# Power.net
KiCad netlist of a schematic drawn in Altium Designer
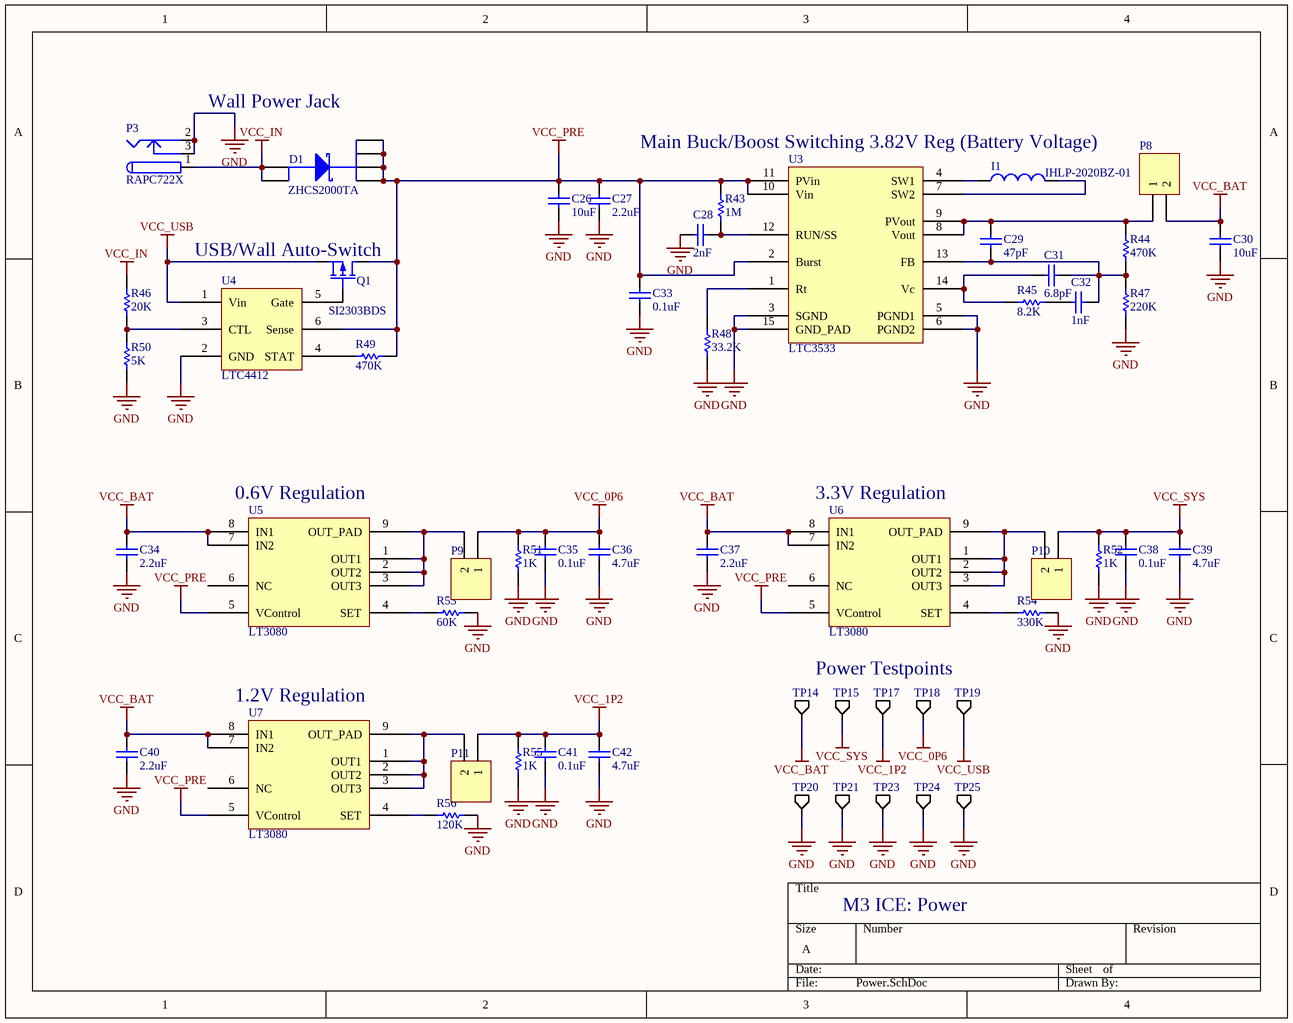
[diagram p0: Power.SchDoc]

(export (version "E")
  (design (tool "Eeschema 10.0.6"))
  (components
    (comp (ref "C26")
      (value "10uF")
      (footprint "0805")
      (description "Capacitor (Semiconductor SIM Model)")
      (fields (field (name "Comment") "Cap Chip") (field (name "PUBLISHER") "Altium Limited"))
      (libsource (lib "M3") (part "Cap Chip"))
    )
    (comp (ref "C27")
      (value "2.2uF")
      (footprint "1608[0603]")
      (description "Capacitor (Semiconductor SIM Model)")
      (fields (field (name "Comment") "Cap Semi") (field (name "PUBLISHER") "Altium Limited"))
      (libsource (lib "Miscellaneous Devices") (part "Cap Semi"))
    )
    (comp (ref "C28")
      (value "2nF")
      (footprint "1608[0603]")
      (description "Capacitor (Semiconductor SIM Model)")
      (fields (field (name "Comment") "Cap Semi") (field (name "PUBLISHER") "Altium Limited"))
      (libsource (lib "Miscellaneous Devices") (part "Cap Semi"))
    )
    (comp (ref "C29")
      (value "47pF")
      (footprint "1608[0603]")
      (description "Capacitor (Semiconductor SIM Model)")
      (fields (field (name "Comment") "Cap Semi") (field (name "PUBLISHER") "Altium Limited"))
      (libsource (lib "Miscellaneous Devices") (part "Cap Semi"))
    )
    (comp (ref "C30")
      (value "10uF")
      (footprint "0805")
      (description "Capacitor (Semiconductor SIM Model)")
      (fields (field (name "Comment") "Cap Chip") (field (name "PUBLISHER") "Altium Limited"))
      (libsource (lib "M3") (part "Cap Chip"))
    )
    (comp (ref "C31")
      (value "6.8pF")
      (footprint "1608[0603]")
      (description "Capacitor (Semiconductor SIM Model)")
      (fields (field (name "Comment") "Cap Semi") (field (name "PUBLISHER") "Altium Limited"))
      (libsource (lib "Miscellaneous Devices") (part "Cap Semi"))
    )
    (comp (ref "C32")
      (value "1nF")
      (footprint "1608[0603]")
      (description "Capacitor (Semiconductor SIM Model)")
      (fields (field (name "Comment") "Cap Semi") (field (name "PUBLISHER") "Altium Limited"))
      (libsource (lib "Miscellaneous Devices") (part "Cap Semi"))
    )
    (comp (ref "C33")
      (value "0.1uF")
      (footprint "1608[0603]")
      (description "Capacitor (Semiconductor SIM Model)")
      (fields (field (name "Comment") "Cap Semi") (field (name "PUBLISHER") "Altium Limited"))
      (libsource (lib "Miscellaneous Devices") (part "Cap Semi"))
    )
    (comp (ref "C34")
      (value "2.2uF")
      (footprint "1608[0603]")
      (description "Capacitor (Semiconductor SIM Model)")
      (fields (field (name "Comment") "Cap Semi") (field (name "PUBLISHER") "Altium Limited"))
      (libsource (lib "Miscellaneous Devices") (part "Cap Semi"))
    )
    (comp (ref "C35")
      (value "0.1uF")
      (footprint "1608[0603]")
      (description "Capacitor (Semiconductor SIM Model)")
      (fields (field (name "Comment") "Cap Semi") (field (name "PUBLISHER") "Altium Limited"))
      (libsource (lib "Miscellaneous Devices") (part "Cap Semi"))
    )
    (comp (ref "C36")
      (value "4.7uF")
      (footprint "0805")
      (description "Capacitor (Semiconductor SIM Model)")
      (fields (field (name "Comment") "Cap Chip") (field (name "PUBLISHER") "Altium Limited"))
      (libsource (lib "M3") (part "Cap Chip"))
    )
    (comp (ref "C37")
      (value "2.2uF")
      (footprint "1608[0603]")
      (description "Capacitor (Semiconductor SIM Model)")
      (fields (field (name "Comment") "Cap Semi") (field (name "PUBLISHER") "Altium Limited"))
      (libsource (lib "Miscellaneous Devices") (part "Cap Semi"))
    )
    (comp (ref "C38")
      (value "0.1uF")
      (footprint "1608[0603]")
      (description "Capacitor (Semiconductor SIM Model)")
      (fields (field (name "Comment") "Cap Semi") (field (name "PUBLISHER") "Altium Limited"))
      (libsource (lib "Miscellaneous Devices") (part "Cap Semi"))
    )
    (comp (ref "C39")
      (value "4.7uF")
      (footprint "0805")
      (description "Capacitor (Semiconductor SIM Model)")
      (fields (field (name "Comment") "Cap Chip") (field (name "PUBLISHER") "Altium Limited"))
      (libsource (lib "M3") (part "Cap Chip"))
    )
    (comp (ref "C40")
      (value "2.2uF")
      (footprint "1608[0603]")
      (description "Capacitor (Semiconductor SIM Model)")
      (fields (field (name "Comment") "Cap Semi") (field (name "PUBLISHER") "Altium Limited"))
      (libsource (lib "Miscellaneous Devices") (part "Cap Semi"))
    )
    (comp (ref "C41")
      (value "0.1uF")
      (footprint "1608[0603]")
      (description "Capacitor (Semiconductor SIM Model)")
      (fields (field (name "Comment") "Cap Semi") (field (name "PUBLISHER") "Altium Limited"))
      (libsource (lib "Miscellaneous Devices") (part "Cap Semi"))
    )
    (comp (ref "C42")
      (value "4.7uF")
      (footprint "0805")
      (description "Capacitor (Semiconductor SIM Model)")
      (fields (field (name "Comment") "Cap Chip") (field (name "PUBLISHER") "Altium Limited"))
      (libsource (lib "M3") (part "Cap Chip"))
    )
    (comp (ref "D1")
      (value "ZHCS2000TA")
      (footprint "SOT23-6_L")
      (description "Schottky Diode")
      (fields (field (name "PUBLISHER") "Altium Limited"))
      (libsource (lib "M3") (part "ZHCS2000TA"))
    )
    (comp (ref "I1")
      (value "IHLP-2020BZ-01")
      (footprint "INDUCTOR_5.49mm_5.18mm")
      (description "IHLP2020BZER2R2M01")
      (libsource (lib "M3") (part "Inductor IHLP-2020BZ-01"))
    )
    (comp (ref "P3")
      (value "RAPC722X")
      (footprint "RAPC722X")
      (description "CONN POWERJACK MINI R/A T/H")
      (libsource (lib "M3") (part "RAPC722X"))
    )
    (comp (ref "P8")
      (value "Header 2")
      (footprint "HDR1X2")
      (description "Header, 2-Pin")
      (fields (field (name "PUBLISHER") "Altium Limited"))
      (libsource (lib "Miscellaneous Connectors") (part "Header 2"))
    )
    (comp (ref "P9")
      (value "Header 2")
      (footprint "HDR1X2")
      (description "Header, 2-Pin")
      (fields (field (name "PUBLISHER") "Altium Limited"))
      (libsource (lib "") (part "Header 2_1"))
    )
    (comp (ref "P10")
      (value "Header 2")
      (footprint "HDR1X2")
      (description "Header, 2-Pin")
      (fields (field (name "PUBLISHER") "Altium Limited"))
      (libsource (lib "") (part "Header 2_1"))
    )
    (comp (ref "P11")
      (value "Header 2")
      (footprint "HDR1X2")
      (description "Header, 2-Pin")
      (fields (field (name "PUBLISHER") "Altium Limited"))
      (libsource (lib "") (part "Header 2_1"))
    )
    (comp (ref "Q1")
      (value "SI2303BDS")
      (footprint "SOT-23_N")
      (description "P-Channel MOSFET")
      (libsource (lib "M3") (part "SI2303BDS"))
    )
    (comp (ref "R43")
      (value "1M")
      (footprint "0603")
      (description "Semiconductor Resistor")
      (fields (field (name "Comment") "Res Chip") (field (name "PUBLISHER") "Altium Limited"))
      (libsource (lib "M3") (part "Res Chip"))
    )
    (comp (ref "R44")
      (value "470K")
      (footprint "0603")
      (description "Semiconductor Resistor")
      (fields (field (name "Comment") "Res Chip") (field (name "PUBLISHER") "Altium Limited"))
      (libsource (lib "M3") (part "Res Chip"))
    )
    (comp (ref "R45")
      (value "8.2K")
      (footprint "0603")
      (description "Semiconductor Resistor")
      (fields (field (name "Comment") "Res Chip") (field (name "PUBLISHER") "Altium Limited"))
      (libsource (lib "M3") (part "Res Chip"))
    )
    (comp (ref "R46")
      (value "20K")
      (footprint "0603")
      (description "Semiconductor Resistor")
      (fields (field (name "Comment") "Res Chip") (field (name "PUBLISHER") "Altium Limited"))
      (libsource (lib "M3") (part "Res Chip"))
    )
    (comp (ref "R47")
      (value "220K")
      (footprint "0603")
      (description "Semiconductor Resistor")
      (fields (field (name "Comment") "Res Chip") (field (name "PUBLISHER") "Altium Limited"))
      (libsource (lib "M3") (part "Res Chip"))
    )
    (comp (ref "R48")
      (value "33.2K")
      (footprint "0603")
      (description "Semiconductor Resistor")
      (fields (field (name "Comment") "Res Chip") (field (name "PUBLISHER") "Altium Limited"))
      (libsource (lib "M3") (part "Res Chip"))
    )
    (comp (ref "R49")
      (value "470K")
      (footprint "0603")
      (description "Semiconductor Resistor")
      (fields (field (name "Comment") "Res Chip") (field (name "PUBLISHER") "Altium Limited"))
      (libsource (lib "M3") (part "Res Chip"))
    )
    (comp (ref "R50")
      (value "5K")
      (footprint "0603")
      (description "Semiconductor Resistor")
      (fields (field (name "Comment") "Res Chip") (field (name "PUBLISHER") "Altium Limited"))
      (libsource (lib "M3") (part "Res Chip"))
    )
    (comp (ref "R51")
      (value "1K")
      (footprint "0603")
      (description "Semiconductor Resistor")
      (fields (field (name "Comment") "Res Chip") (field (name "PUBLISHER") "Altium Limited"))
      (libsource (lib "M3") (part "Res Chip"))
    )
    (comp (ref "R52")
      (value "1K")
      (footprint "0603")
      (description "Semiconductor Resistor")
      (fields (field (name "Comment") "Res Chip") (field (name "PUBLISHER") "Altium Limited"))
      (libsource (lib "M3") (part "Res Chip"))
    )
    (comp (ref "R53")
      (value "60K")
      (footprint "0603")
      (description "Semiconductor Resistor")
      (fields (field (name "Comment") "Res Chip") (field (name "PUBLISHER") "Altium Limited"))
      (libsource (lib "M3") (part "Res Chip"))
    )
    (comp (ref "R54")
      (value "330K")
      (footprint "0603")
      (description "Semiconductor Resistor")
      (fields (field (name "Comment") "Res Chip") (field (name "PUBLISHER") "Altium Limited"))
      (libsource (lib "M3") (part "Res Chip"))
    )
    (comp (ref "R55")
      (value "1K")
      (footprint "0603")
      (description "Semiconductor Resistor")
      (fields (field (name "Comment") "Res Chip") (field (name "PUBLISHER") "Altium Limited"))
      (libsource (lib "M3") (part "Res Chip"))
    )
    (comp (ref "R56")
      (value "120K")
      (footprint "0603")
      (description "Semiconductor Resistor")
      (fields (field (name "Comment") "Res Chip") (field (name "PUBLISHER") "Altium Limited"))
      (libsource (lib "M3") (part "Res Chip"))
    )
    (comp (ref "TP14") (value "TP") (footprint "TP") (libsource (lib "M3") (part "TP")))
    (comp (ref "TP15") (value "TP") (footprint "TP") (libsource (lib "M3") (part "TP")))
    (comp (ref "TP17") (value "TP") (footprint "TP") (libsource (lib "M3") (part "TP")))
    (comp (ref "TP18") (value "TP") (footprint "TP") (libsource (lib "M3") (part "TP")))
    (comp (ref "TP19") (value "TP") (footprint "TP") (libsource (lib "M3") (part "TP")))
    (comp (ref "TP20") (value "TP") (footprint "TP") (libsource (lib "M3") (part "TP")))
    (comp (ref "TP21") (value "TP") (footprint "TP") (libsource (lib "M3") (part "TP")))
    (comp (ref "TP23") (value "TP") (footprint "TP") (libsource (lib "M3") (part "TP")))
    (comp (ref "TP24") (value "TP") (footprint "TP") (libsource (lib "M3") (part "TP")))
    (comp (ref "TP25") (value "TP") (footprint "TP") (libsource (lib "M3") (part "TP")))
    (comp (ref "U3") (value "LTC3533") (footprint "14-WFDFN") (libsource (lib "M3") (part "LTC3533")))
    (comp (ref "U4") (value "LTC4412") (footprint "SOT23-6_L") (libsource (lib "M3") (part "LTC4412")))
    (comp (ref "U5") (value "LT3080") (footprint "MSOP-8") (libsource (lib "M3") (part "LT3080")))
    (comp (ref "U6") (value "LT3080") (footprint "MSOP-8") (libsource (lib "M3") (part "LT3080")))
    (comp (ref "U7") (value "LT3080") (footprint "MSOP-8") (libsource (lib "M3") (part "LT3080")))
  )
  (nets
    (net (code "1") (name "GND") (class "Default")
      (node (ref "C26") (pin "1") (pinfunction "1_1") (pintype "passive"))
      (node (ref "C27") (pin "1") (pinfunction "1_1") (pintype "passive"))
      (node (ref "C28") (pin "2") (pinfunction "2_2") (pintype "passive"))
      (node (ref "C30") (pin "1") (pinfunction "1_1") (pintype "passive"))
      (node (ref "C33") (pin "1") (pinfunction "1_1") (pintype "passive"))
      (node (ref "C34") (pin "1") (pinfunction "1_1") (pintype "passive"))
      (node (ref "C35") (pin "1") (pinfunction "1_1") (pintype "passive"))
      (node (ref "C36") (pin "1") (pinfunction "1_1") (pintype "passive"))
      (node (ref "C37") (pin "1") (pinfunction "1_1") (pintype "passive"))
      (node (ref "C38") (pin "1") (pinfunction "1_1") (pintype "passive"))
      (node (ref "C39") (pin "1") (pinfunction "1_1") (pintype "passive"))
      (node (ref "C40") (pin "1") (pinfunction "1_1") (pintype "passive"))
      (node (ref "C41") (pin "1") (pinfunction "1_1") (pintype "passive"))
      (node (ref "C42") (pin "1") (pinfunction "1_1") (pintype "passive"))
      (node (ref "P3") (pin "2") (pinfunction "2_2") (pintype "power_in"))
      (node (ref "P3") (pin "3") (pinfunction "3_3") (pintype "power_in"))
      (node (ref "R47") (pin "2") (pinfunction "2_2") (pintype "passive"))
      (node (ref "R48") (pin "1") (pinfunction "1_1") (pintype "passive"))
      (node (ref "R50") (pin "1") (pinfunction "1_1") (pintype "passive"))
      (node (ref "R51") (pin "1") (pinfunction "1_1") (pintype "passive"))
      (node (ref "R52") (pin "1") (pinfunction "1_1") (pintype "passive"))
      (node (ref "R53") (pin "1") (pinfunction "1_1") (pintype "passive"))
      (node (ref "R54") (pin "1") (pinfunction "1_1") (pintype "passive"))
      (node (ref "R55") (pin "1") (pinfunction "1_1") (pintype "passive"))
      (node (ref "R56") (pin "1") (pinfunction "1_1") (pintype "passive"))
      (node (ref "TP20") (pin "1") (pinfunction "A_1") (pintype "passive"))
      (node (ref "TP21") (pin "1") (pinfunction "A_1") (pintype "passive"))
      (node (ref "TP23") (pin "1") (pinfunction "A_1") (pintype "passive"))
      (node (ref "TP24") (pin "1") (pinfunction "A_1") (pintype "passive"))
      (node (ref "TP25") (pin "1") (pinfunction "A_1") (pintype "passive"))
      (node (ref "U3") (pin "15") (pinfunction "GND_PAD_15") (pintype "passive"))
      (node (ref "U3") (pin "3") (pinfunction "SGND_3") (pintype "passive"))
      (node (ref "U3") (pin "5") (pinfunction "PGND1_5") (pintype "passive"))
      (node (ref "U3") (pin "6") (pinfunction "PGND2_6") (pintype "passive"))
      (node (ref "U4") (pin "2") (pinfunction "GND_2") (pintype "passive"))
    )
    (net (code "2") (name "Net-(C32-Pad2)") (class "Default")
      (node (ref "C32") (pin "2") (pinfunction "2_2") (pintype "passive"))
      (node (ref "R45") (pin "1") (pinfunction "1_1") (pintype "passive"))
    )
    (net (code "3") (name "Net-(Q1-G)") (class "Default")
      (node (ref "Q1") (pin "1") (pinfunction "G_1") (pintype "passive"))
      (node (ref "U4") (pin "5") (pinfunction "Gate_5") (pintype "passive"))
    )
    (net (code "4") (name "Net-(U3-FB)") (class "Default")
      (node (ref "C29") (pin "1") (pinfunction "1_1") (pintype "passive"))
      (node (ref "C31") (pin "1") (pinfunction "1_1") (pintype "passive"))
      (node (ref "C32") (pin "1") (pinfunction "1_1") (pintype "passive"))
      (node (ref "R44") (pin "1") (pinfunction "1_1") (pintype "passive"))
      (node (ref "R47") (pin "1") (pinfunction "1_1") (pintype "passive"))
      (node (ref "U3") (pin "13") (pinfunction "FB_13") (pintype "passive"))
    )
    (net (code "5") (name "Net-(U3-PVout)") (class "Default")
      (node (ref "C29") (pin "2") (pinfunction "2_2") (pintype "passive"))
      (node (ref "P8") (pin "1") (pinfunction "1_1") (pintype "passive"))
      (node (ref "R44") (pin "2") (pinfunction "2_2") (pintype "passive"))
      (node (ref "U3") (pin "8") (pinfunction "Vout_8") (pintype "passive"))
      (node (ref "U3") (pin "9") (pinfunction "PVout_9") (pintype "passive"))
    )
    (net (code "6") (name "Net-(U3-RUN{slash}SS)") (class "Default")
      (node (ref "C28") (pin "1") (pinfunction "1_1") (pintype "passive"))
      (node (ref "R43") (pin "1") (pinfunction "1_1") (pintype "passive"))
      (node (ref "U3") (pin "12") (pinfunction "RUN/SS_12") (pintype "passive"))
    )
    (net (code "7") (name "Net-(U3-Rt)") (class "Default")
      (node (ref "R48") (pin "2") (pinfunction "2_2") (pintype "passive"))
      (node (ref "U3") (pin "1") (pinfunction "Rt_1") (pintype "passive"))
    )
    (net (code "8") (name "Net-(U3-SW1)") (class "Default")
      (node (ref "I1") (pin "1") (pinfunction "1_1") (pintype "passive"))
      (node (ref "U3") (pin "4") (pinfunction "SW1_4") (pintype "passive"))
    )
    (net (code "9") (name "Net-(U3-SW2)") (class "Default")
      (node (ref "I1") (pin "2") (pinfunction "2_2") (pintype "passive"))
      (node (ref "U3") (pin "7") (pinfunction "SW2_7") (pintype "passive"))
    )
    (net (code "10") (name "Net-(U3-Vc)") (class "Default")
      (node (ref "C31") (pin "2") (pinfunction "2_2") (pintype "passive"))
      (node (ref "R45") (pin "2") (pinfunction "2_2") (pintype "passive"))
      (node (ref "U3") (pin "14") (pinfunction "Vc_14") (pintype "passive"))
    )
    (net (code "11") (name "Net-(U4-CTL)") (class "Default")
      (node (ref "R46") (pin "1") (pinfunction "1_1") (pintype "passive"))
      (node (ref "R50") (pin "2") (pinfunction "2_2") (pintype "passive"))
      (node (ref "U4") (pin "3") (pinfunction "CTL_3") (pintype "passive"))
    )
    (net (code "12") (name "Net-(U4-STAT)") (class "Default")
      (node (ref "R49") (pin "2") (pinfunction "2_2") (pintype "passive"))
      (node (ref "U4") (pin "4") (pinfunction "STAT_4") (pintype "passive"))
    )
    (net (code "13") (name "Net-(U5-OUT1)") (class "Default")
      (node (ref "P9") (pin "2") (pinfunction "2_2") (pintype "passive"))
      (node (ref "U5") (pin "1") (pinfunction "OUT1_1") (pintype "passive"))
      (node (ref "U5") (pin "2") (pinfunction "OUT2_2") (pintype "passive"))
      (node (ref "U5") (pin "3") (pinfunction "OUT3_3") (pintype "passive"))
      (node (ref "U5") (pin "9") (pinfunction "OUT_PAD_9") (pintype "passive"))
    )
    (net (code "14") (name "Net-(U5-SET)") (class "Default")
      (node (ref "R53") (pin "2") (pinfunction "2_2") (pintype "passive"))
      (node (ref "U5") (pin "4") (pinfunction "SET_4") (pintype "passive"))
    )
    (net (code "15") (name "Net-(U6-OUT1)") (class "Default")
      (node (ref "P10") (pin "2") (pinfunction "2_2") (pintype "passive"))
      (node (ref "U6") (pin "1") (pinfunction "OUT1_1") (pintype "passive"))
      (node (ref "U6") (pin "2") (pinfunction "OUT2_2") (pintype "passive"))
      (node (ref "U6") (pin "3") (pinfunction "OUT3_3") (pintype "passive"))
      (node (ref "U6") (pin "9") (pinfunction "OUT_PAD_9") (pintype "passive"))
    )
    (net (code "16") (name "Net-(U6-SET)") (class "Default")
      (node (ref "R54") (pin "2") (pinfunction "2_2") (pintype "passive"))
      (node (ref "U6") (pin "4") (pinfunction "SET_4") (pintype "passive"))
    )
    (net (code "17") (name "Net-(U7-OUT1)") (class "Default")
      (node (ref "P11") (pin "2") (pinfunction "2_2") (pintype "passive"))
      (node (ref "U7") (pin "1") (pinfunction "OUT1_1") (pintype "passive"))
      (node (ref "U7") (pin "2") (pinfunction "OUT2_2") (pintype "passive"))
      (node (ref "U7") (pin "3") (pinfunction "OUT3_3") (pintype "passive"))
      (node (ref "U7") (pin "9") (pinfunction "OUT_PAD_9") (pintype "passive"))
    )
    (net (code "18") (name "Net-(U7-SET)") (class "Default")
      (node (ref "R56") (pin "2") (pinfunction "2_2") (pintype "passive"))
      (node (ref "U7") (pin "4") (pinfunction "SET_4") (pintype "passive"))
    )
    (net (code "19") (name "VCC_0P6") (class "Default")
      (node (ref "C35") (pin "2") (pinfunction "2_2") (pintype "passive"))
      (node (ref "C36") (pin "2") (pinfunction "2_2") (pintype "passive"))
      (node (ref "P9") (pin "1") (pinfunction "1_1") (pintype "passive"))
      (node (ref "R51") (pin "2") (pinfunction "2_2") (pintype "passive"))
      (node (ref "TP18") (pin "1") (pinfunction "A_1") (pintype "passive"))
    )
    (net (code "20") (name "VCC_1P2") (class "Default")
      (node (ref "C41") (pin "2") (pinfunction "2_2") (pintype "passive"))
      (node (ref "C42") (pin "2") (pinfunction "2_2") (pintype "passive"))
      (node (ref "P11") (pin "1") (pinfunction "1_1") (pintype "passive"))
      (node (ref "R55") (pin "2") (pinfunction "2_2") (pintype "passive"))
      (node (ref "TP17") (pin "1") (pinfunction "A_1") (pintype "passive"))
    )
    (net (code "21") (name "VCC_BAT") (class "Default")
      (node (ref "C30") (pin "2") (pinfunction "2_2") (pintype "passive"))
      (node (ref "C34") (pin "2") (pinfunction "2_2") (pintype "passive"))
      (node (ref "C37") (pin "2") (pinfunction "2_2") (pintype "passive"))
      (node (ref "C40") (pin "2") (pinfunction "2_2") (pintype "passive"))
      (node (ref "P8") (pin "2") (pinfunction "2_2") (pintype "passive"))
      (node (ref "TP14") (pin "1") (pinfunction "A_1") (pintype "passive"))
      (node (ref "U5") (pin "7") (pinfunction "IN2_7") (pintype "passive"))
      (node (ref "U5") (pin "8") (pinfunction "IN1_8") (pintype "passive"))
      (node (ref "U6") (pin "7") (pinfunction "IN2_7") (pintype "passive"))
      (node (ref "U6") (pin "8") (pinfunction "IN1_8") (pintype "passive"))
      (node (ref "U7") (pin "7") (pinfunction "IN2_7") (pintype "passive"))
      (node (ref "U7") (pin "8") (pinfunction "IN1_8") (pintype "passive"))
    )
    (net (code "22") (name "VCC_IN") (class "Default")
      (node (ref "D1") (pin "3") (pinfunction "A_3") (pintype "passive"))
      (node (ref "D1") (pin "4") (pinfunction "A_4") (pintype "passive"))
      (node (ref "P3") (pin "1") (pinfunction "1_1") (pintype "power_in"))
      (node (ref "R46") (pin "2") (pinfunction "2_2") (pintype "passive"))
    )
    (net (code "23") (name "VCC_PRE") (class "Default")
      (node (ref "C26") (pin "2") (pinfunction "2_2") (pintype "passive"))
      (node (ref "C27") (pin "2") (pinfunction "2_2") (pintype "passive"))
      (node (ref "C33") (pin "2") (pinfunction "2_2") (pintype "passive"))
      (node (ref "D1") (pin "1") (pinfunction "K_1") (pintype "passive"))
      (node (ref "D1") (pin "2") (pinfunction "K_2") (pintype "passive"))
      (node (ref "D1") (pin "5") (pinfunction "K_5") (pintype "passive"))
      (node (ref "D1") (pin "6") (pinfunction "K_6") (pintype "passive"))
      (node (ref "Q1") (pin "3") (pinfunction "D_3") (pintype "passive"))
      (node (ref "R43") (pin "2") (pinfunction "2_2") (pintype "passive"))
      (node (ref "R49") (pin "1") (pinfunction "1_1") (pintype "passive"))
      (node (ref "U3") (pin "10") (pinfunction "Vin_10") (pintype "passive"))
      (node (ref "U3") (pin "11") (pinfunction "PVin_11") (pintype "passive"))
      (node (ref "U3") (pin "2") (pinfunction "Burst_2") (pintype "passive"))
      (node (ref "U4") (pin "6") (pinfunction "Sense_6") (pintype "passive"))
      (node (ref "U5") (pin "5") (pinfunction "VControl_5") (pintype "passive"))
      (node (ref "U6") (pin "5") (pinfunction "VControl_5") (pintype "passive"))
      (node (ref "U7") (pin "5") (pinfunction "VControl_5") (pintype "passive"))
    )
    (net (code "24") (name "VCC_SYS") (class "Default")
      (node (ref "C38") (pin "2") (pinfunction "2_2") (pintype "passive"))
      (node (ref "C39") (pin "2") (pinfunction "2_2") (pintype "passive"))
      (node (ref "P10") (pin "1") (pinfunction "1_1") (pintype "passive"))
      (node (ref "R52") (pin "2") (pinfunction "2_2") (pintype "passive"))
      (node (ref "TP15") (pin "1") (pinfunction "A_1") (pintype "passive"))
    )
    (net (code "25") (name "VCC_USB") (class "Default")
      (node (ref "Q1") (pin "2") (pinfunction "S_2") (pintype "passive"))
      (node (ref "TP19") (pin "1") (pinfunction "A_1") (pintype "passive"))
      (node (ref "U4") (pin "1") (pinfunction "Vin_1") (pintype "passive"))
    )
    (net (code "26") (name "unconnected-(U5-NC-Pad6)") (class "Default")
      (node (ref "U5") (pin "6") (pinfunction "NC_6") (pintype "passive"))
    )
    (net (code "27") (name "unconnected-(U6-NC-Pad6)") (class "Default")
      (node (ref "U6") (pin "6") (pinfunction "NC_6") (pintype "passive"))
    )
    (net (code "28") (name "unconnected-(U7-NC-Pad6)") (class "Default")
      (node (ref "U7") (pin "6") (pinfunction "NC_6") (pintype "passive"))
    )
  )
)
